# T11-MIDIThereminCPU.net
KiCad netlist of a schematic drawn in EAGLE
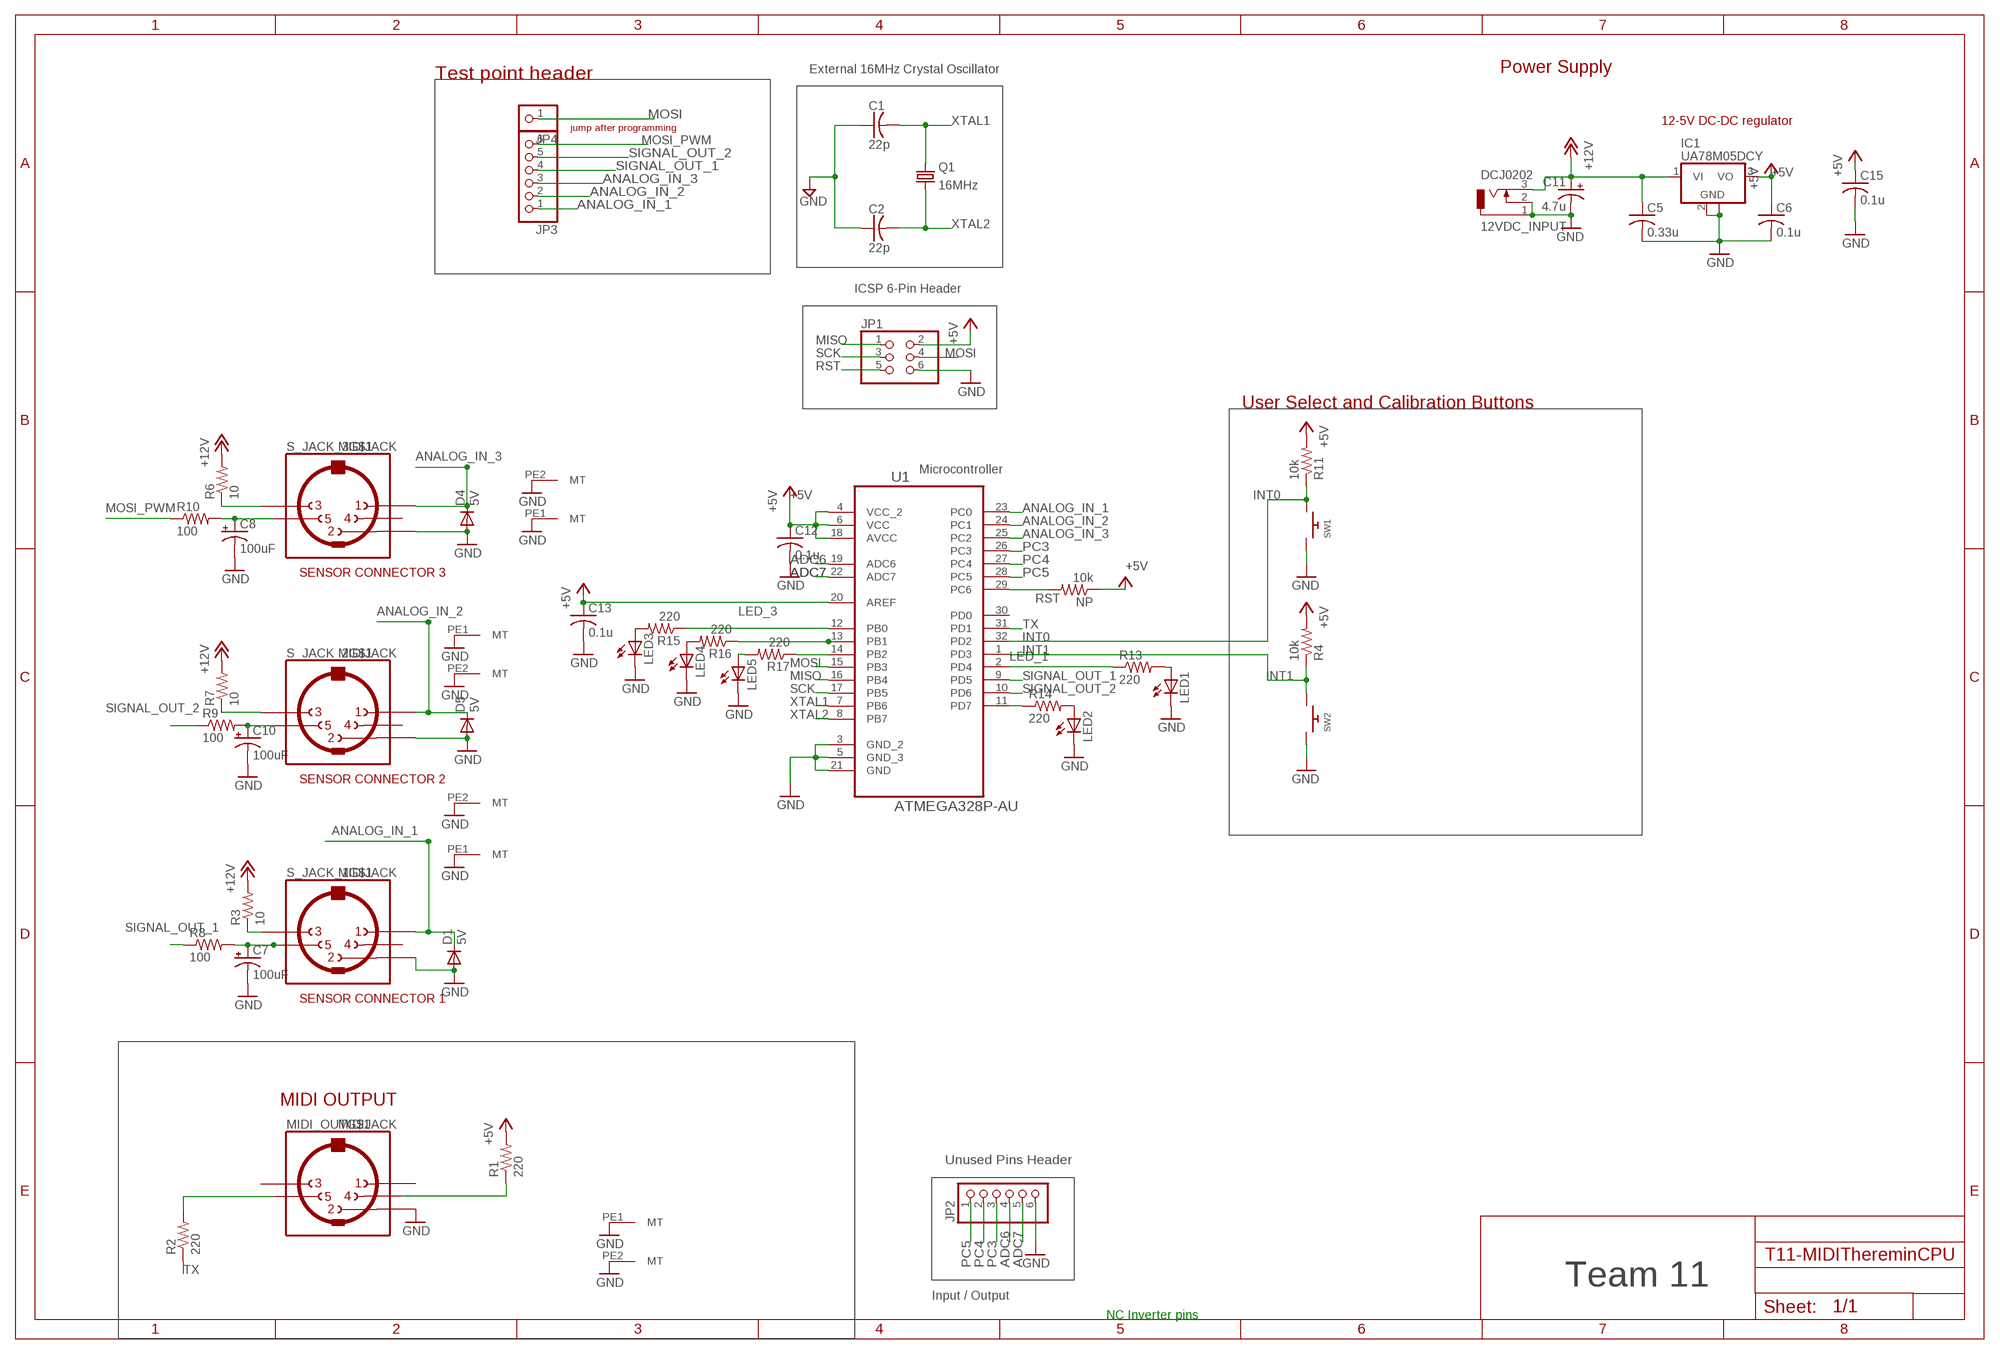
[diagram p0: schematic, sheet 1]

(export (version "E")
  (design (tool "Eeschema 10.0.6"))
  (components
    (comp (ref "12VDC_INPUT")
      (value "DCJ0202")
      (footprint "eagle-import:DCJ0202")
      (libsource (lib "eagle-import") (part "DCJ0202"))
    )
    (comp (ref "C1")
      (value "22p")
      (footprint "eagle-import:C0805")
      (libsource (lib "eagle-import") (part "C-USC0805"))
    )
    (comp (ref "C2")
      (value "22p")
      (footprint "eagle-import:C0805")
      (libsource (lib "eagle-import") (part "C-USC0805"))
    )
    (comp (ref "C5")
      (value "0.33u")
      (footprint "eagle-import:C0805")
      (libsource (lib "eagle-import") (part "C-USC0805"))
    )
    (comp (ref "C6")
      (value "0.1u")
      (footprint "eagle-import:C0805")
      (libsource (lib "eagle-import") (part "C-USC0805"))
    )
    (comp (ref "C7")
      (value "100uF")
      (footprint "eagle-import:E3,5-8")
      (libsource (lib "eagle-import") (part "CPOL-USE3.5-8"))
    )
    (comp (ref "C8")
      (value "100uF")
      (footprint "eagle-import:E3,5-8")
      (libsource (lib "eagle-import") (part "CPOL-USE3.5-8"))
    )
    (comp (ref "C10")
      (value "100uF")
      (footprint "eagle-import:E3,5-8")
      (libsource (lib "eagle-import") (part "CPOL-USE3.5-8"))
    )
    (comp (ref "C11")
      (value "4.7u")
      (footprint "eagle-import:E3,5-8")
      (libsource (lib "eagle-import") (part "CPOL-USE3.5-8"))
    )
    (comp (ref "C12")
      (value "0.1u")
      (footprint "eagle-import:C0805")
      (libsource (lib "eagle-import") (part "C-USC0805"))
    )
    (comp (ref "C13")
      (value "0.1u")
      (footprint "eagle-import:C0805")
      (libsource (lib "eagle-import") (part "C-USC0805"))
    )
    (comp (ref "C15")
      (value "0.1u")
      (footprint "eagle-import:C0805")
      (libsource (lib "eagle-import") (part "C-USC0805"))
    )
    (comp (ref "D1")
      (value "5V")
      (footprint "eagle-import:DO35-7")
      (libsource (lib "eagle-import") (part "1N4148DO35-7"))
    )
    (comp (ref "D4")
      (value "5V")
      (footprint "eagle-import:DO35-7")
      (libsource (lib "eagle-import") (part "1N4148DO35-7"))
    )
    (comp (ref "D5")
      (value "5V")
      (footprint "eagle-import:DO35-7")
      (libsource (lib "eagle-import") (part "1N4148DO35-7"))
    )
    (comp (ref "IC1")
      (value "UA78M05DCY")
      (footprint "eagle-import:SOT223")
      (libsource (lib "eagle-import") (part "UA78MDCY05"))
    )
    (comp (ref "JP1")
      (value "PINHD-2X3")
      (footprint "eagle-import:2X03")
      (libsource (lib "eagle-import") (part "PINHD-2X3"))
    )
    (comp (ref "JP2")
      (value "PINHD-1X6")
      (footprint "eagle-import:1X06")
      (libsource (lib "eagle-import") (part "PINHD-1X6"))
    )
    (comp (ref "JP3")
      (value "PINHD-1X6")
      (footprint "eagle-import:1X06")
      (libsource (lib "eagle-import") (part "PINHD-1X6"))
    )
    (comp (ref "JP4")
      (value "PINHD-1X1")
      (footprint "eagle-import:1X01")
      (libsource (lib "eagle-import") (part "PINHD-1X1"))
    )
    (comp (ref "LED1")
      (value "LED3MM")
      (footprint "eagle-import:LED3MM")
      (libsource (lib "eagle-import") (part "LED3MM"))
    )
    (comp (ref "LED2")
      (value "LED3MM")
      (footprint "eagle-import:LED3MM")
      (libsource (lib "eagle-import") (part "LED3MM"))
    )
    (comp (ref "LED3")
      (value "LED3MM")
      (footprint "eagle-import:LED3MM")
      (libsource (lib "eagle-import") (part "LED3MM"))
    )
    (comp (ref "LED4")
      (value "LED3MM")
      (footprint "eagle-import:LED3MM")
      (libsource (lib "eagle-import") (part "LED3MM"))
    )
    (comp (ref "LED5")
      (value "LED3MM")
      (footprint "eagle-import:LED3MM")
      (libsource (lib "eagle-import") (part "LED3MM"))
    )
    (comp (ref "MIDI_OUT")
      (value "MIDIJACK")
      (footprint "eagle-import:CP-2350")
      (libsource (lib "eagle-import") (part "MIDIJACK"))
    )
    (comp (ref "NP")
      (value "10k")
      (footprint "eagle-import:R0805")
      (libsource (lib "eagle-import") (part "R-US_R0805"))
    )
    (comp (ref "Q1")
      (value "16MHz")
      (footprint "eagle-import:SM49")
      (libsource (lib "eagle-import") (part "CRYSTALSM49"))
    )
    (comp (ref "R1")
      (value "220")
      (footprint "eagle-import:R0805")
      (libsource (lib "eagle-import") (part "R-US_R0805"))
    )
    (comp (ref "R2")
      (value "220")
      (footprint "eagle-import:M0805")
      (libsource (lib "eagle-import") (part "R-US_M0805"))
    )
    (comp (ref "R3")
      (value "10")
      (footprint "eagle-import:R0805")
      (libsource (lib "eagle-import") (part "R-US_R0805"))
    )
    (comp (ref "R4")
      (value "10k")
      (footprint "eagle-import:R0805")
      (libsource (lib "eagle-import") (part "R-US_R0805"))
    )
    (comp (ref "R6")
      (value "10")
      (footprint "eagle-import:M0805")
      (libsource (lib "eagle-import") (part "R-US_M0805"))
    )
    (comp (ref "R7")
      (value "10")
      (footprint "eagle-import:R0805")
      (libsource (lib "eagle-import") (part "R-US_R0805"))
    )
    (comp (ref "R8")
      (value "100")
      (footprint "eagle-import:R0805")
      (libsource (lib "eagle-import") (part "R-US_R0805"))
    )
    (comp (ref "R9")
      (value "100")
      (footprint "eagle-import:R0805")
      (libsource (lib "eagle-import") (part "R-US_R0805"))
    )
    (comp (ref "R10")
      (value "100")
      (footprint "eagle-import:M0805")
      (libsource (lib "eagle-import") (part "R-US_M0805"))
    )
    (comp (ref "R11")
      (value "10k")
      (footprint "eagle-import:R0805")
      (libsource (lib "eagle-import") (part "R-US_R0805"))
    )
    (comp (ref "R13")
      (value "220")
      (footprint "eagle-import:R0805")
      (libsource (lib "eagle-import") (part "R-US_R0805"))
    )
    (comp (ref "R14")
      (value "220")
      (footprint "eagle-import:R0805")
      (libsource (lib "eagle-import") (part "R-US_R0805"))
    )
    (comp (ref "R15")
      (value "220")
      (footprint "eagle-import:R0805")
      (libsource (lib "eagle-import") (part "R-US_R0805"))
    )
    (comp (ref "R16")
      (value "220")
      (footprint "eagle-import:R0805")
      (libsource (lib "eagle-import") (part "R-US_R0805"))
    )
    (comp (ref "R17")
      (value "220")
      (footprint "eagle-import:R0805")
      (libsource (lib "eagle-import") (part "R-US_R0805"))
    )
    (comp (ref "SW1")
      (value "SWITCH_PUSHBUTTONSOFTTOUCHSMD_SJ")
      (footprint "eagle-import:PUSHBUTTON_SMD_SJ")
      (libsource (lib "eagle-import") (part "SWITCH_PUSHBUTTONSOFTTOUCHSMD_SJ"))
    )
    (comp (ref "SW2")
      (value "SWITCH_PUSHBUTTONSOFTTOUCHSMD_SJ")
      (footprint "eagle-import:PUSHBUTTON_SMD_SJ")
      (libsource (lib "eagle-import") (part "SWITCH_PUSHBUTTONSOFTTOUCHSMD_SJ"))
    )
    (comp (ref "S_JACK_1")
      (value "MIDIJACK")
      (footprint "eagle-import:CP-2350")
      (libsource (lib "eagle-import") (part "MIDIJACK"))
    )
    (comp (ref "S_JACK_2")
      (value "MIDIJACK")
      (footprint "eagle-import:CP-2350")
      (libsource (lib "eagle-import") (part "MIDIJACK"))
    )
    (comp (ref "S_JACK_3")
      (value "MIDIJACK")
      (footprint "eagle-import:CP-2350")
      (libsource (lib "eagle-import") (part "MIDIJACK"))
    )
    (comp (ref "U1")
      (value "ATMEGA328P-AU")
      (footprint "eagle-import:QFP80P900X900X120-32N")
      (libsource (lib "eagle-import") (part "ATMEGA328P-AU"))
    )
  )
  (nets
    (net (code "1") (name "+5V") (class "Default")
      (node (ref "C12") (pin "1") (pinfunction "1_1") (pintype "passive"))
      (node (ref "C13") (pin "1") (pinfunction "1_1") (pintype "passive"))
      (node (ref "C15") (pin "1") (pinfunction "1_1") (pintype "passive"))
      (node (ref "C6") (pin "1") (pinfunction "1_1") (pintype "passive"))
      (node (ref "IC1") (pin "3") (pinfunction "VO_3") (pintype "passive"))
      (node (ref "JP1") (pin "2") (pinfunction "2_2") (pintype "passive"))
      (node (ref "NP") (pin "1") (pinfunction "1_1") (pintype "passive"))
      (node (ref "R1") (pin "2") (pinfunction "2_2") (pintype "passive"))
      (node (ref "R11") (pin "2") (pinfunction "2_2") (pintype "passive"))
      (node (ref "R4") (pin "2") (pinfunction "2_2") (pintype "passive"))
      (node (ref "U1") (pin "18") (pinfunction "AVCC_18") (pintype "power_in"))
      (node (ref "U1") (pin "20") (pinfunction "AREF_20") (pintype "input"))
      (node (ref "U1") (pin "4") (pinfunction "VCC_2_4") (pintype "power_in"))
      (node (ref "U1") (pin "6") (pinfunction "VCC_6") (pintype "power_in"))
    )
    (net (code "2") (name "+12V") (class "Default")
      (node (ref "12VDC_INPUT") (pin "3") (pinfunction "3_3") (pintype "passive"))
      (node (ref "C11") (pin "+") (pinfunction "+_+") (pintype "passive"))
      (node (ref "C5") (pin "1") (pinfunction "1_1") (pintype "passive"))
      (node (ref "IC1") (pin "1") (pinfunction "VI_1") (pintype "input"))
      (node (ref "R3") (pin "2") (pinfunction "2_2") (pintype "passive"))
      (node (ref "R6") (pin "2") (pinfunction "2_2") (pintype "passive"))
      (node (ref "R7") (pin "2") (pinfunction "2_2") (pintype "passive"))
    )
    (net (code "3") (name "/ADC6") (class "Default")
      (node (ref "JP2") (pin "4") (pinfunction "4_4") (pintype "passive"))
      (node (ref "U1") (pin "19") (pinfunction "ADC6_19") (pintype "input"))
    )
    (net (code "4") (name "/ADC7") (class "Default")
      (node (ref "JP2") (pin "5") (pinfunction "5_5") (pintype "passive"))
      (node (ref "U1") (pin "22") (pinfunction "ADC7_22") (pintype "input"))
    )
    (net (code "5") (name "/ANALOG_IN_1") (class "Default")
      (node (ref "D1") (pin "C") (pinfunction "C_C") (pintype "passive"))
      (node (ref "JP3") (pin "1") (pinfunction "1_1") (pintype "passive"))
      (node (ref "S_JACK_1") (pin "1") (pinfunction "1_1") (pintype "passive"))
      (node (ref "U1") (pin "23") (pinfunction "PC0_23") (pintype "bidirectional"))
    )
    (net (code "6") (name "/ANALOG_IN_2") (class "Default")
      (node (ref "D5") (pin "C") (pinfunction "C_C") (pintype "passive"))
      (node (ref "JP3") (pin "2") (pinfunction "2_2") (pintype "passive"))
      (node (ref "S_JACK_2") (pin "1") (pinfunction "1_1") (pintype "passive"))
      (node (ref "U1") (pin "24") (pinfunction "PC1_24") (pintype "bidirectional"))
    )
    (net (code "7") (name "/ANALOG_IN_3") (class "Default")
      (node (ref "D4") (pin "C") (pinfunction "C_C") (pintype "passive"))
      (node (ref "JP3") (pin "3") (pinfunction "3_3") (pintype "passive"))
      (node (ref "S_JACK_3") (pin "1") (pinfunction "1_1") (pintype "passive"))
      (node (ref "U1") (pin "25") (pinfunction "PC2_25") (pintype "bidirectional"))
    )
    (net (code "8") (name "/INT0") (class "Default")
      (node (ref "R11") (pin "1") (pinfunction "1_1") (pintype "passive"))
      (node (ref "SW1") (pin "P$2") (pinfunction "P$2_P$2") (pintype "passive"))
      (node (ref "U1") (pin "32") (pinfunction "PD2_32") (pintype "bidirectional"))
    )
    (net (code "9") (name "/INT1") (class "Default")
      (node (ref "R4") (pin "1") (pinfunction "1_1") (pintype "passive"))
      (node (ref "SW2") (pin "P$2") (pinfunction "P$2_P$2") (pintype "passive"))
      (node (ref "U1") (pin "1") (pinfunction "PD3_1") (pintype "bidirectional"))
    )
    (net (code "10") (name "/LED_1") (class "Default")
      (node (ref "R13") (pin "1") (pinfunction "1_1") (pintype "passive"))
      (node (ref "U1") (pin "2") (pinfunction "PD4_2") (pintype "bidirectional"))
    )
    (net (code "11") (name "/LED_3") (class "Default")
      (node (ref "R15") (pin "1") (pinfunction "1_1") (pintype "passive"))
      (node (ref "U1") (pin "12") (pinfunction "PB0_12") (pintype "bidirectional"))
    )
    (net (code "12") (name "/MISO") (class "Default")
      (node (ref "JP1") (pin "1") (pinfunction "1_1") (pintype "passive"))
      (node (ref "U1") (pin "16") (pinfunction "PB4_16") (pintype "bidirectional"))
    )
    (net (code "13") (name "/MOSI") (class "Default")
      (node (ref "JP1") (pin "4") (pinfunction "4_4") (pintype "passive"))
      (node (ref "JP4") (pin "1") (pinfunction "1_1") (pintype "passive"))
      (node (ref "U1") (pin "15") (pinfunction "PB3_15") (pintype "bidirectional"))
    )
    (net (code "14") (name "/MOSI_PWM") (class "Default")
      (node (ref "JP3") (pin "6") (pinfunction "6_6") (pintype "passive"))
      (node (ref "R10") (pin "1") (pinfunction "1_1") (pintype "passive"))
    )
    (net (code "15") (name "/PC3") (class "Default")
      (node (ref "JP2") (pin "3") (pinfunction "3_3") (pintype "passive"))
      (node (ref "U1") (pin "26") (pinfunction "PC3_26") (pintype "bidirectional"))
    )
    (net (code "16") (name "/PC4") (class "Default")
      (node (ref "JP2") (pin "2") (pinfunction "2_2") (pintype "passive"))
      (node (ref "U1") (pin "27") (pinfunction "PC4_27") (pintype "bidirectional"))
    )
    (net (code "17") (name "/PC5") (class "Default")
      (node (ref "JP2") (pin "1") (pinfunction "1_1") (pintype "passive"))
      (node (ref "U1") (pin "28") (pinfunction "PC5_28") (pintype "bidirectional"))
    )
    (net (code "18") (name "/RST") (class "Default")
      (node (ref "JP1") (pin "5") (pinfunction "5_5") (pintype "passive"))
      (node (ref "NP") (pin "2") (pinfunction "2_2") (pintype "passive"))
      (node (ref "U1") (pin "29") (pinfunction "PC6_29") (pintype "bidirectional"))
    )
    (net (code "19") (name "/SCK") (class "Default")
      (node (ref "JP1") (pin "3") (pinfunction "3_3") (pintype "passive"))
      (node (ref "U1") (pin "17") (pinfunction "PB5_17") (pintype "bidirectional"))
    )
    (net (code "20") (name "/SIGNAL_OUT_1") (class "Default")
      (node (ref "JP3") (pin "4") (pinfunction "4_4") (pintype "passive"))
      (node (ref "R8") (pin "1") (pinfunction "1_1") (pintype "passive"))
      (node (ref "U1") (pin "9") (pinfunction "PD5_9") (pintype "bidirectional"))
    )
    (net (code "21") (name "/SIGNAL_OUT_2") (class "Default")
      (node (ref "JP3") (pin "5") (pinfunction "5_5") (pintype "passive"))
      (node (ref "R9") (pin "1") (pinfunction "1_1") (pintype "passive"))
      (node (ref "U1") (pin "10") (pinfunction "PD6_10") (pintype "bidirectional"))
    )
    (net (code "22") (name "/TX") (class "Default")
      (node (ref "R2") (pin "1") (pinfunction "1_1") (pintype "passive"))
      (node (ref "U1") (pin "31") (pinfunction "PD1_31") (pintype "bidirectional"))
    )
    (net (code "23") (name "/XTAL1") (class "Default")
      (node (ref "C1") (pin "2") (pinfunction "2_2") (pintype "passive"))
      (node (ref "Q1") (pin "2") (pinfunction "2_2") (pintype "passive"))
      (node (ref "U1") (pin "7") (pinfunction "PB6_7") (pintype "bidirectional"))
    )
    (net (code "24") (name "/XTAL2") (class "Default")
      (node (ref "C2") (pin "2") (pinfunction "2_2") (pintype "passive"))
      (node (ref "Q1") (pin "1") (pinfunction "1_1") (pintype "passive"))
      (node (ref "U1") (pin "8") (pinfunction "PB7_8") (pintype "bidirectional"))
    )
    (net (code "25") (name "GND") (class "Default")
      (node (ref "12VDC_INPUT") (pin "1") (pinfunction "1_1") (pintype "passive"))
      (node (ref "12VDC_INPUT") (pin "2") (pinfunction "2_2") (pintype "passive"))
      (node (ref "C1") (pin "1") (pinfunction "1_1") (pintype "passive"))
      (node (ref "C10") (pin "-") (pinfunction "-_-") (pintype "passive"))
      (node (ref "C11") (pin "-") (pinfunction "-_-") (pintype "passive"))
      (node (ref "C12") (pin "2") (pinfunction "2_2") (pintype "passive"))
      (node (ref "C13") (pin "2") (pinfunction "2_2") (pintype "passive"))
      (node (ref "C15") (pin "2") (pinfunction "2_2") (pintype "passive"))
      (node (ref "C2") (pin "1") (pinfunction "1_1") (pintype "passive"))
      (node (ref "C5") (pin "2") (pinfunction "2_2") (pintype "passive"))
      (node (ref "C6") (pin "2") (pinfunction "2_2") (pintype "passive"))
      (node (ref "C7") (pin "-") (pinfunction "-_-") (pintype "passive"))
      (node (ref "C8") (pin "-") (pinfunction "-_-") (pintype "passive"))
      (node (ref "D1") (pin "A") (pinfunction "A_A") (pintype "passive"))
      (node (ref "D4") (pin "A") (pinfunction "A_A") (pintype "passive"))
      (node (ref "D5") (pin "A") (pinfunction "A_A") (pintype "passive"))
      (node (ref "IC1") (pin "2") (pinfunction "GND_2") (pintype "passive"))
      (node (ref "IC1") (pin "4") (pinfunction "GND_4") (pintype "passive"))
      (node (ref "JP1") (pin "6") (pinfunction "6_6") (pintype "passive"))
      (node (ref "JP2") (pin "6") (pinfunction "6_6") (pintype "passive"))
      (node (ref "LED1") (pin "K") (pinfunction "C_K") (pintype "passive"))
      (node (ref "LED2") (pin "K") (pinfunction "C_K") (pintype "passive"))
      (node (ref "LED3") (pin "K") (pinfunction "C_K") (pintype "passive"))
      (node (ref "LED4") (pin "K") (pinfunction "C_K") (pintype "passive"))
      (node (ref "LED5") (pin "K") (pinfunction "C_K") (pintype "passive"))
      (node (ref "MIDI_OUT") (pin "2") (pinfunction "2_2") (pintype "passive"))
      (node (ref "MIDI_OUT") (pin "PE1") (pinfunction "MT_PE1") (pintype "passive"))
      (node (ref "MIDI_OUT") (pin "PE2") (pinfunction "MT_PE2") (pintype "passive"))
      (node (ref "SW1") (pin "P$1") (pinfunction "P$1_P$1") (pintype "passive"))
      (node (ref "SW2") (pin "P$1") (pinfunction "P$1_P$1") (pintype "passive"))
      (node (ref "S_JACK_1") (pin "2") (pinfunction "2_2") (pintype "passive"))
      (node (ref "S_JACK_1") (pin "PE1") (pinfunction "MT_PE1") (pintype "passive"))
      (node (ref "S_JACK_1") (pin "PE2") (pinfunction "MT_PE2") (pintype "passive"))
      (node (ref "S_JACK_2") (pin "2") (pinfunction "2_2") (pintype "passive"))
      (node (ref "S_JACK_2") (pin "PE1") (pinfunction "MT_PE1") (pintype "passive"))
      (node (ref "S_JACK_2") (pin "PE2") (pinfunction "MT_PE2") (pintype "passive"))
      (node (ref "S_JACK_3") (pin "2") (pinfunction "2_2") (pintype "passive"))
      (node (ref "S_JACK_3") (pin "PE1") (pinfunction "MT_PE1") (pintype "passive"))
      (node (ref "S_JACK_3") (pin "PE2") (pinfunction "MT_PE2") (pintype "passive"))
      (node (ref "U1") (pin "21") (pinfunction "GND_21") (pintype "passive"))
      (node (ref "U1") (pin "3") (pinfunction "GND_2_3") (pintype "passive"))
      (node (ref "U1") (pin "5") (pinfunction "GND_3_5") (pintype "passive"))
    )
    (net (code "26") (name "Net-(C7-Pad+)") (class "Default")
      (node (ref "C7") (pin "+") (pinfunction "+_+") (pintype "passive"))
      (node (ref "R8") (pin "2") (pinfunction "2_2") (pintype "passive"))
      (node (ref "S_JACK_1") (pin "5") (pinfunction "5_5") (pintype "passive"))
    )
    (net (code "27") (name "Net-(C8-Pad+)") (class "Default")
      (node (ref "C8") (pin "+") (pinfunction "+_+") (pintype "passive"))
      (node (ref "R10") (pin "2") (pinfunction "2_2") (pintype "passive"))
      (node (ref "S_JACK_3") (pin "5") (pinfunction "5_5") (pintype "passive"))
    )
    (net (code "28") (name "Net-(C10-Pad+)") (class "Default")
      (node (ref "C10") (pin "+") (pinfunction "+_+") (pintype "passive"))
      (node (ref "R9") (pin "2") (pinfunction "2_2") (pintype "passive"))
      (node (ref "S_JACK_2") (pin "5") (pinfunction "5_5") (pintype "passive"))
    )
    (net (code "29") (name "Net-(LED1-PadA)") (class "Default")
      (node (ref "LED1") (pin "A") (pinfunction "A_A") (pintype "passive"))
      (node (ref "R13") (pin "2") (pinfunction "2_2") (pintype "passive"))
    )
    (net (code "30") (name "Net-(LED2-PadA)") (class "Default")
      (node (ref "LED2") (pin "A") (pinfunction "A_A") (pintype "passive"))
      (node (ref "R14") (pin "2") (pinfunction "2_2") (pintype "passive"))
    )
    (net (code "31") (name "Net-(LED3-PadA)") (class "Default")
      (node (ref "LED3") (pin "A") (pinfunction "A_A") (pintype "passive"))
      (node (ref "R15") (pin "2") (pinfunction "2_2") (pintype "passive"))
    )
    (net (code "32") (name "Net-(LED4-PadA)") (class "Default")
      (node (ref "LED4") (pin "A") (pinfunction "A_A") (pintype "passive"))
      (node (ref "R16") (pin "2") (pinfunction "2_2") (pintype "passive"))
    )
    (net (code "33") (name "Net-(LED5-PadA)") (class "Default")
      (node (ref "LED5") (pin "A") (pinfunction "A_A") (pintype "passive"))
      (node (ref "R17") (pin "2") (pinfunction "2_2") (pintype "passive"))
    )
    (net (code "34") (name "Net-(MIDI_OUT-Pad4)") (class "Default")
      (node (ref "MIDI_OUT") (pin "4") (pinfunction "4_4") (pintype "passive"))
      (node (ref "R1") (pin "1") (pinfunction "1_1") (pintype "passive"))
    )
    (net (code "35") (name "Net-(MIDI_OUT-Pad5)") (class "Default")
      (node (ref "MIDI_OUT") (pin "5") (pinfunction "5_5") (pintype "passive"))
      (node (ref "R2") (pin "2") (pinfunction "2_2") (pintype "passive"))
    )
    (net (code "36") (name "Net-(R3-Pad1)") (class "Default")
      (node (ref "R3") (pin "1") (pinfunction "1_1") (pintype "passive"))
      (node (ref "S_JACK_1") (pin "3") (pinfunction "3_3") (pintype "passive"))
    )
    (net (code "37") (name "Net-(R6-Pad1)") (class "Default")
      (node (ref "R6") (pin "1") (pinfunction "1_1") (pintype "passive"))
      (node (ref "S_JACK_3") (pin "3") (pinfunction "3_3") (pintype "passive"))
    )
    (net (code "38") (name "Net-(R7-Pad1)") (class "Default")
      (node (ref "R7") (pin "1") (pinfunction "1_1") (pintype "passive"))
      (node (ref "S_JACK_2") (pin "3") (pinfunction "3_3") (pintype "passive"))
    )
    (net (code "39") (name "Net-(U1-PB1)") (class "Default")
      (node (ref "R16") (pin "1") (pinfunction "1_1") (pintype "passive"))
      (node (ref "U1") (pin "13") (pinfunction "PB1_13") (pintype "bidirectional"))
    )
    (net (code "40") (name "Net-(U1-PB2)") (class "Default")
      (node (ref "R17") (pin "1") (pinfunction "1_1") (pintype "passive"))
      (node (ref "U1") (pin "14") (pinfunction "PB2_14") (pintype "bidirectional"))
    )
    (net (code "41") (name "Net-(U1-PD7)") (class "Default")
      (node (ref "R14") (pin "1") (pinfunction "1_1") (pintype "passive"))
      (node (ref "U1") (pin "11") (pinfunction "PD7_11") (pintype "bidirectional"))
    )
    (net (code "42") (name "unconnected-(MIDI_OUT-Pad1)") (class "Default")
      (node (ref "MIDI_OUT") (pin "1") (pinfunction "1_1") (pintype "passive"))
    )
    (net (code "43") (name "unconnected-(MIDI_OUT-Pad3)") (class "Default")
      (node (ref "MIDI_OUT") (pin "3") (pinfunction "3_3") (pintype "passive"))
    )
    (net (code "44") (name "unconnected-(S_JACK_1-Pad4)") (class "Default")
      (node (ref "S_JACK_1") (pin "4") (pinfunction "4_4") (pintype "passive"))
    )
    (net (code "45") (name "unconnected-(S_JACK_2-Pad4)") (class "Default")
      (node (ref "S_JACK_2") (pin "4") (pinfunction "4_4") (pintype "passive"))
    )
    (net (code "46") (name "unconnected-(S_JACK_3-Pad4)") (class "Default")
      (node (ref "S_JACK_3") (pin "4") (pinfunction "4_4") (pintype "passive"))
    )
    (net (code "47") (name "unconnected-(U1-PD0-Pad30)") (class "Default")
      (node (ref "U1") (pin "30") (pinfunction "PD0_30") (pintype "bidirectional"))
    )
  )
)
